# MS20v2.net
KiCad netlist of a schematic drawn in EAGLE
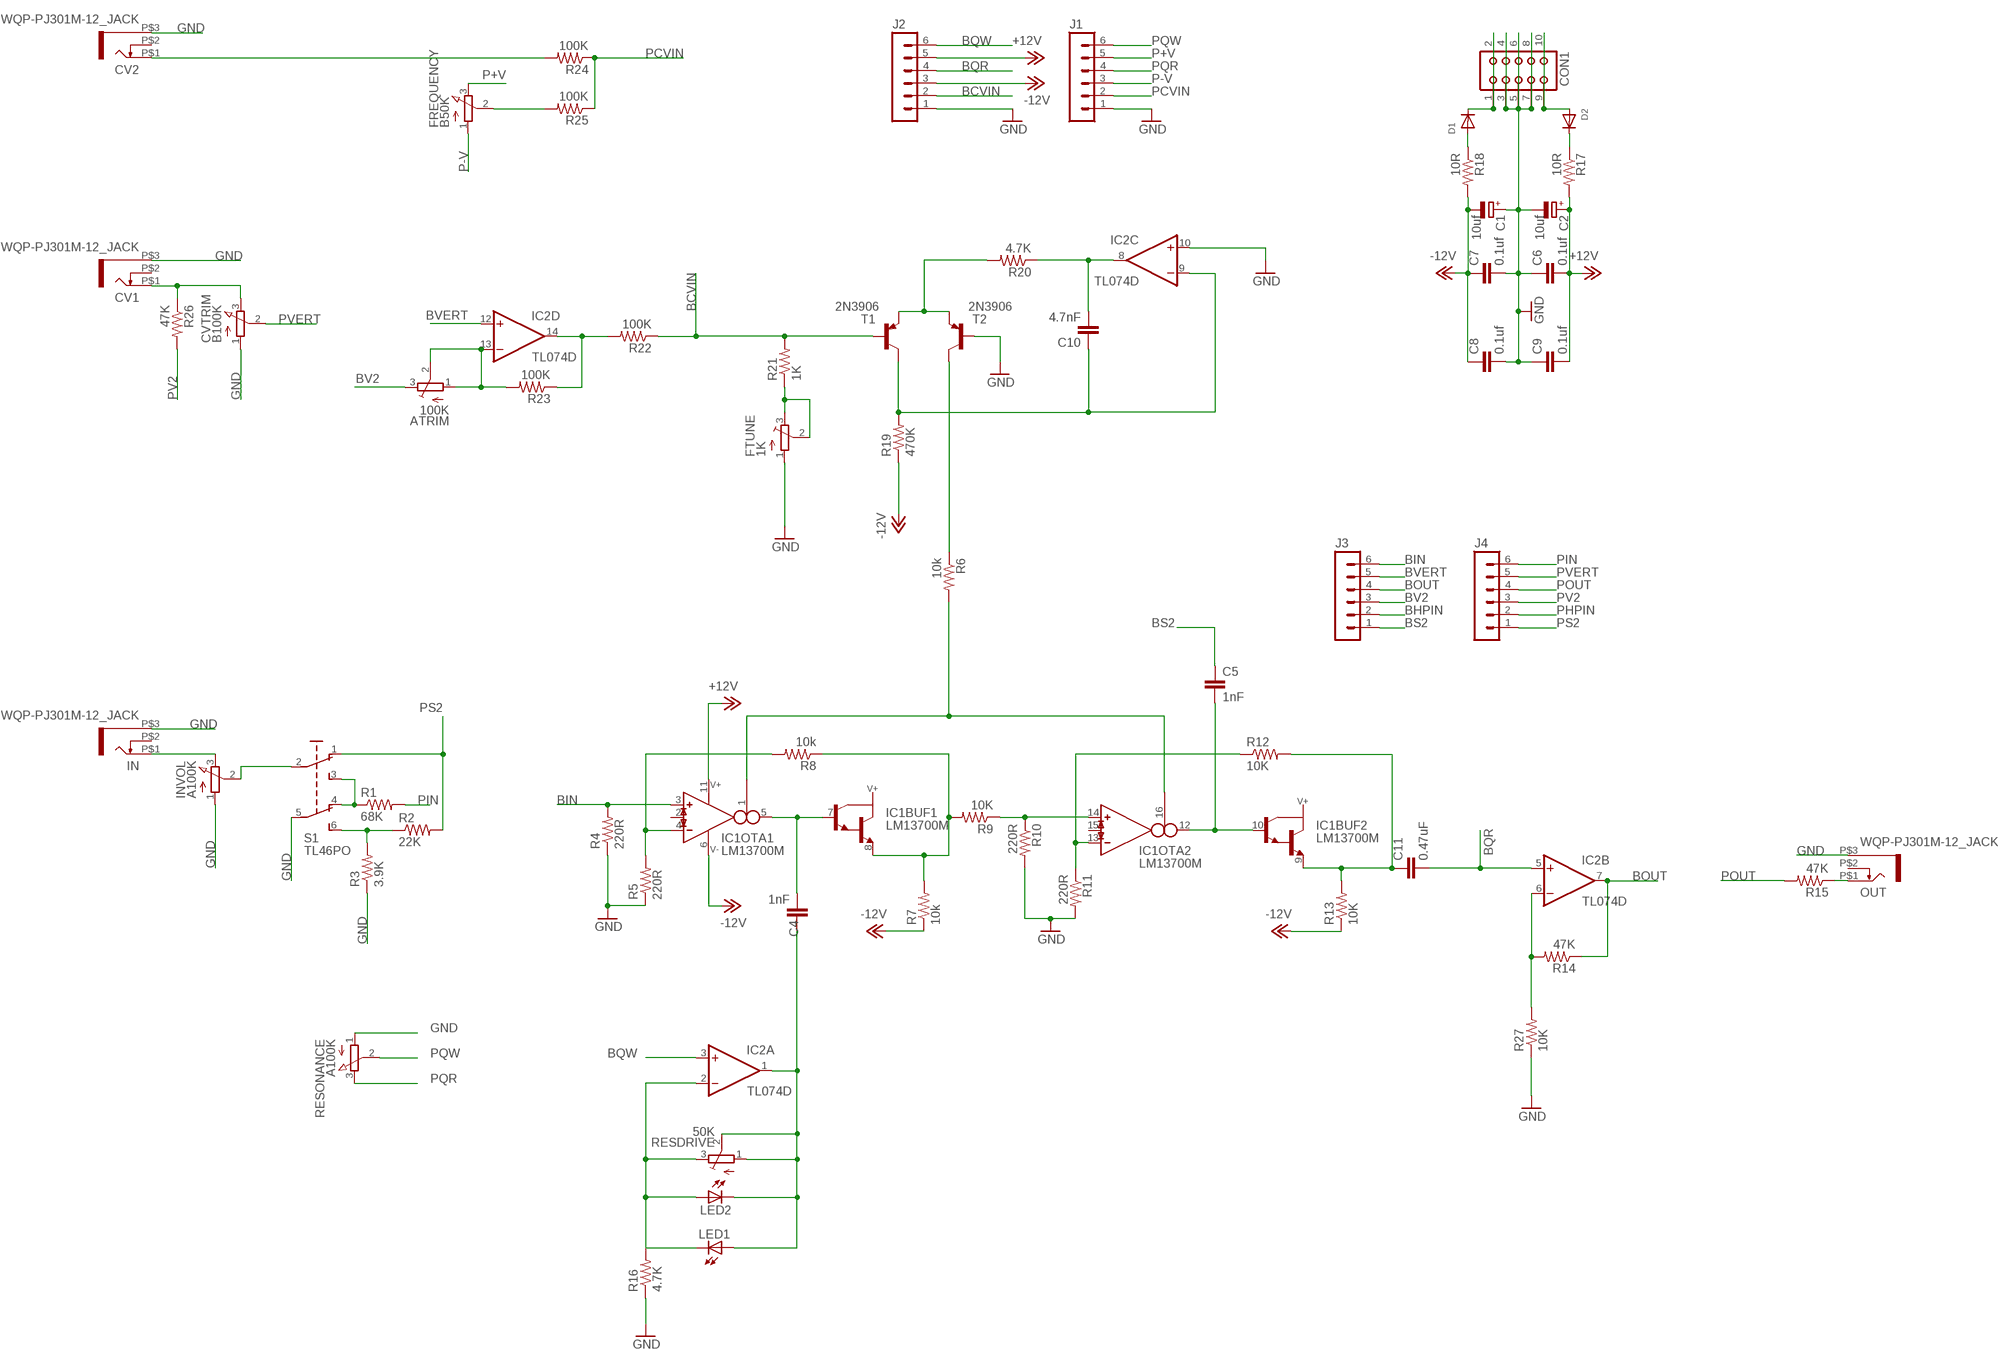
[diagram p0: schematic, sheet 1]

(export (version "E")
  (design (tool "Eeschema 10.0.6"))
  (components
    (comp (ref "ATRIM")
      (value "100K")
      (footprint "eagle-import:TC33X")
      (libsource (lib "eagle-import") (part "TRIMPOTTC33X"))
    )
    (comp (ref "C1")
      (value "10uf")
      (footprint "eagle-import:153CLV-0405")
      (libsource (lib "eagle-import") (part "CPOL-EU153CLV-0405"))
    )
    (comp (ref "C2")
      (value "10uf")
      (footprint "eagle-import:153CLV-0405")
      (libsource (lib "eagle-import") (part "CPOL-EU153CLV-0405"))
    )
    (comp (ref "C4")
      (value "1nF")
      (footprint "eagle-import:C0603")
      (libsource (lib "eagle-import") (part "C-EUC0603"))
    )
    (comp (ref "C5")
      (value "1nF")
      (footprint "eagle-import:C0603")
      (libsource (lib "eagle-import") (part "C-EUC0603"))
    )
    (comp (ref "C6")
      (value "0.1uf")
      (footprint "eagle-import:C0603")
      (libsource (lib "eagle-import") (part "C-EUC0603"))
    )
    (comp (ref "C7")
      (value "0.1uf")
      (footprint "eagle-import:C0603")
      (libsource (lib "eagle-import") (part "C-EUC0603"))
    )
    (comp (ref "C8")
      (value "0.1uf")
      (footprint "eagle-import:C0603")
      (libsource (lib "eagle-import") (part "C-EUC0603"))
    )
    (comp (ref "C9")
      (value "0.1uf")
      (footprint "eagle-import:C0603")
      (libsource (lib "eagle-import") (part "C-EUC0603"))
    )
    (comp (ref "C10")
      (value "4.7nF")
      (footprint "eagle-import:C0603")
      (libsource (lib "eagle-import") (part "C-EUC0603"))
    )
    (comp (ref "C11")
      (value "0.47uF")
      (footprint "eagle-import:C0603")
      (libsource (lib "eagle-import") (part "C-EUC0603"))
    )
    (comp (ref "CON1")
      (value "CON10")
      (footprint "eagle-import:CON10")
      (libsource (lib "eagle-import") (part "CON10"))
    )
    (comp (ref "CV1")
      (value "WQP-PJ301M-12_JACK")
      (footprint "eagle-import:WQP-PJ301M-12_JACK")
      (libsource (lib "eagle-import") (part "WQP-PJ301M-12_JACK"))
    )
    (comp (ref "CV2")
      (value "WQP-PJ301M-12_JACK")
      (footprint "eagle-import:WQP-PJ301M-12_JACK")
      (libsource (lib "eagle-import") (part "WQP-PJ301M-12_JACK"))
    )
    (comp (ref "CVTRIM")
      (value "B100K")
      (footprint "eagle-import:EVUF")
      (libsource (lib "eagle-import") (part "EVUAF2"))
    )
    (comp (ref "D1")
      (value "DIODESOD-123")
      (footprint "eagle-import:SOD-123")
      (libsource (lib "eagle-import") (part "DIODESOD-123"))
    )
    (comp (ref "D2")
      (value "DIODESOD-123")
      (footprint "eagle-import:SOD-123")
      (libsource (lib "eagle-import") (part "DIODESOD-123"))
    )
    (comp (ref "FREQUENCY")
      (value "B50K")
      (footprint "eagle-import:EVUF")
      (libsource (lib "eagle-import") (part "EVUAF2"))
    )
    (comp (ref "FTUNE")
      (value "1K")
      (footprint "eagle-import:TC33X")
      (libsource (lib "eagle-import") (part "TRIMPOTTC33X"))
    )
    (comp (ref "IC1")
      (value "LM13700M")
      (footprint "eagle-import:SO16")
      (libsource (lib "eagle-import") (part "LM13700M"))
    )
    (comp (ref "IC2")
      (value "TL074D")
      (footprint "eagle-import:SO14")
      (libsource (lib "eagle-import") (part "TL074D"))
    )
    (comp (ref "IN")
      (value "WQP-PJ301M-12_JACK")
      (footprint "eagle-import:WQP-PJ301M-12_JACK")
      (libsource (lib "eagle-import") (part "WQP-PJ301M-12_JACK"))
    )
    (comp (ref "INVOL")
      (value "A100K")
      (footprint "eagle-import:EVUF")
      (libsource (lib "eagle-import") (part "EVUAF2"))
    )
    (comp (ref "J1")
      (value "MA06-1")
      (footprint "eagle-import:MA06-1")
      (libsource (lib "eagle-import") (part "MA06-1"))
    )
    (comp (ref "J2")
      (value "MA06-1")
      (footprint "eagle-import:MA06-1")
      (libsource (lib "eagle-import") (part "MA06-1"))
    )
    (comp (ref "J3")
      (value "MA06-1")
      (footprint "eagle-import:MA06-1")
      (libsource (lib "eagle-import") (part "MA06-1"))
    )
    (comp (ref "J4")
      (value "MA06-1")
      (footprint "eagle-import:MA06-1")
      (libsource (lib "eagle-import") (part "MA06-1"))
    )
    (comp (ref "LED1")
      (value "LED3MM")
      (footprint "eagle-import:LED3MM")
      (libsource (lib "eagle-import") (part "LED3MM"))
    )
    (comp (ref "LED2")
      (value "LED3MM")
      (footprint "eagle-import:LED3MM")
      (libsource (lib "eagle-import") (part "LED3MM"))
    )
    (comp (ref "OUT")
      (value "WQP-PJ301M-12_JACK")
      (footprint "eagle-import:WQP-PJ301M-12_JACK")
      (libsource (lib "eagle-import") (part "WQP-PJ301M-12_JACK"))
    )
    (comp (ref "R1")
      (value "68K")
      (footprint "eagle-import:R0603")
      (libsource (lib "eagle-import") (part "R-US_R0603"))
    )
    (comp (ref "R2")
      (value "22K")
      (footprint "eagle-import:R0603")
      (libsource (lib "eagle-import") (part "R-US_R0603"))
    )
    (comp (ref "R3")
      (value "3.9K")
      (footprint "eagle-import:R0603")
      (libsource (lib "eagle-import") (part "R-US_R0603"))
    )
    (comp (ref "R4")
      (value "220R")
      (footprint "eagle-import:R0603")
      (libsource (lib "eagle-import") (part "R-US_R0603"))
    )
    (comp (ref "R5")
      (value "220R")
      (footprint "eagle-import:R0603")
      (libsource (lib "eagle-import") (part "R-US_R0603"))
    )
    (comp (ref "R6")
      (value "10k")
      (footprint "eagle-import:R0603")
      (libsource (lib "eagle-import") (part "R-US_R0603"))
    )
    (comp (ref "R7")
      (value "10k")
      (footprint "eagle-import:R0603")
      (libsource (lib "eagle-import") (part "R-US_R0603"))
    )
    (comp (ref "R8")
      (value "10k")
      (footprint "eagle-import:R0603")
      (libsource (lib "eagle-import") (part "R-US_R0603"))
    )
    (comp (ref "R9")
      (value "10K")
      (footprint "eagle-import:R0603")
      (libsource (lib "eagle-import") (part "R-US_R0603"))
    )
    (comp (ref "R10")
      (value "220R")
      (footprint "eagle-import:R0603")
      (libsource (lib "eagle-import") (part "R-US_R0603"))
    )
    (comp (ref "R11")
      (value "220R")
      (footprint "eagle-import:R0603")
      (libsource (lib "eagle-import") (part "R-US_R0603"))
    )
    (comp (ref "R12")
      (value "10K")
      (footprint "eagle-import:R0603")
      (libsource (lib "eagle-import") (part "R-US_R0603"))
    )
    (comp (ref "R13")
      (value "10K")
      (footprint "eagle-import:R0603")
      (libsource (lib "eagle-import") (part "R-US_R0603"))
    )
    (comp (ref "R14")
      (value "47K")
      (footprint "eagle-import:R0603")
      (libsource (lib "eagle-import") (part "R-US_R0603"))
    )
    (comp (ref "R15")
      (value "47K")
      (footprint "eagle-import:R0603")
      (libsource (lib "eagle-import") (part "R-US_R0603"))
    )
    (comp (ref "R16")
      (value "4.7K")
      (footprint "eagle-import:R0603")
      (libsource (lib "eagle-import") (part "R-US_R0603"))
    )
    (comp (ref "R17")
      (value "10R")
      (footprint "eagle-import:R0603")
      (libsource (lib "eagle-import") (part "R-US_R0603"))
    )
    (comp (ref "R18")
      (value "10R")
      (footprint "eagle-import:R0603")
      (libsource (lib "eagle-import") (part "R-US_R0603"))
    )
    (comp (ref "R19")
      (value "470K")
      (footprint "eagle-import:R0603")
      (libsource (lib "eagle-import") (part "R-US_R0603"))
    )
    (comp (ref "R20")
      (value "4.7K")
      (footprint "eagle-import:R0603")
      (libsource (lib "eagle-import") (part "R-US_R0603"))
    )
    (comp (ref "R21")
      (value "1K")
      (footprint "eagle-import:R0603")
      (libsource (lib "eagle-import") (part "R-US_R0603"))
    )
    (comp (ref "R22")
      (value "100K")
      (footprint "eagle-import:R0603")
      (libsource (lib "eagle-import") (part "R-US_R0603"))
    )
    (comp (ref "R23")
      (value "100K")
      (footprint "eagle-import:R0603")
      (libsource (lib "eagle-import") (part "R-US_R0603"))
    )
    (comp (ref "R24")
      (value "100K")
      (footprint "eagle-import:R0603")
      (libsource (lib "eagle-import") (part "R-US_R0603"))
    )
    (comp (ref "R25")
      (value "100K")
      (footprint "eagle-import:R0603")
      (libsource (lib "eagle-import") (part "R-US_R0603"))
    )
    (comp (ref "R26")
      (value "47K")
      (footprint "eagle-import:R0603")
      (libsource (lib "eagle-import") (part "R-US_R0603"))
    )
    (comp (ref "R27")
      (value "10K")
      (footprint "eagle-import:R0603")
      (libsource (lib "eagle-import") (part "R-US_R0603"))
    )
    (comp (ref "RESDRIVE")
      (value "50K")
      (footprint "eagle-import:TC33X")
      (libsource (lib "eagle-import") (part "TRIMPOTTC33X"))
    )
    (comp (ref "RESONANCE")
      (value "A100K")
      (footprint "eagle-import:EVUF")
      (libsource (lib "eagle-import") (part "EVUAF2"))
    )
    (comp (ref "S1")
      (value "TL46PO")
      (footprint "eagle-import:TL4XPO")
      (libsource (lib "eagle-import") (part "TL46PO"))
    )
    (comp (ref "T1")
      (value "2N3906")
      (footprint "eagle-import:SOT23-BEC")
      (libsource (lib "eagle-import") (part "-PNP-SOT23-BECMMBT3906LT1"))
    )
    (comp (ref "T2")
      (value "2N3906")
      (footprint "eagle-import:SOT23-BEC")
      (libsource (lib "eagle-import") (part "-PNP-SOT23-BECMMBT3906LT1"))
    )
  )
  (nets
    (net (code "1") (name "+12V") (class "Default")
      (node (ref "C2") (pin "+") (pinfunction "+_+") (pintype "passive"))
      (node (ref "C6") (pin "2") (pinfunction "2_2") (pintype "passive"))
      (node (ref "C9") (pin "2") (pinfunction "2_2") (pintype "passive"))
      (node (ref "IC1") (pin "11") (pinfunction "V+_11") (pintype "power_in"))
      (node (ref "J2") (pin "5") (pinfunction "5_5") (pintype "passive"))
      (node (ref "R17") (pin "2") (pinfunction "2_2") (pintype "passive"))
    )
    (net (code "2") (name "-12V") (class "Default")
      (node (ref "C1") (pin "-") (pinfunction "-_-") (pintype "passive"))
      (node (ref "C7") (pin "1") (pinfunction "1_1") (pintype "passive"))
      (node (ref "C8") (pin "1") (pinfunction "1_1") (pintype "passive"))
      (node (ref "IC1") (pin "6") (pinfunction "V-_6") (pintype "power_in"))
      (node (ref "J2") (pin "3") (pinfunction "3_3") (pintype "passive"))
      (node (ref "R13") (pin "1") (pinfunction "1_1") (pintype "passive"))
      (node (ref "R18") (pin "2") (pinfunction "2_2") (pintype "passive"))
      (node (ref "R19") (pin "1") (pinfunction "1_1") (pintype "passive"))
      (node (ref "R7") (pin "1") (pinfunction "1_1") (pintype "passive"))
    )
    (net (code "3") (name "/BCVIN") (class "Default")
      (node (ref "J2") (pin "2") (pinfunction "2_2") (pintype "passive"))
      (node (ref "R21") (pin "2") (pinfunction "2_2") (pintype "passive"))
      (node (ref "R22") (pin "1") (pinfunction "1_1") (pintype "passive"))
      (node (ref "T1") (pin "B") (pinfunction "B_B") (pintype "passive"))
    )
    (net (code "4") (name "/BHPIN") (class "Default")
      (node (ref "J3") (pin "2") (pinfunction "2_2") (pintype "passive"))
    )
    (net (code "5") (name "/BIN") (class "Default")
      (node (ref "IC1") (pin "3") (pinfunction "IN_P_3") (pintype "input"))
      (node (ref "J3") (pin "6") (pinfunction "6_6") (pintype "passive"))
      (node (ref "R4") (pin "2") (pinfunction "2_2") (pintype "passive"))
    )
    (net (code "6") (name "/BOUT") (class "Default")
      (node (ref "IC2") (pin "7") (pinfunction "OUT_7") (pintype "output"))
      (node (ref "J3") (pin "4") (pinfunction "4_4") (pintype "passive"))
      (node (ref "R14") (pin "1") (pinfunction "1_1") (pintype "passive"))
    )
    (net (code "7") (name "/BQR") (class "Default")
      (node (ref "C11") (pin "2") (pinfunction "2_2") (pintype "passive"))
      (node (ref "IC2") (pin "5") (pinfunction "+IN_5") (pintype "input"))
      (node (ref "J2") (pin "4") (pinfunction "4_4") (pintype "passive"))
    )
    (net (code "8") (name "/BQW") (class "Default")
      (node (ref "IC2") (pin "3") (pinfunction "+IN_3") (pintype "input"))
      (node (ref "J2") (pin "6") (pinfunction "6_6") (pintype "passive"))
    )
    (net (code "9") (name "/BS2") (class "Default")
      (node (ref "C5") (pin "1") (pinfunction "1_1") (pintype "passive"))
      (node (ref "J3") (pin "1") (pinfunction "1_1") (pintype "passive"))
    )
    (net (code "10") (name "/BV2") (class "Default")
      (node (ref "ATRIM") (pin "3") (pinfunction "E_3") (pintype "passive"))
      (node (ref "J3") (pin "3") (pinfunction "3_3") (pintype "passive"))
    )
    (net (code "11") (name "/BVERT") (class "Default")
      (node (ref "IC2") (pin "12") (pinfunction "+IN_12") (pintype "input"))
      (node (ref "J3") (pin "5") (pinfunction "5_5") (pintype "passive"))
    )
    (net (code "12") (name "/P+V") (class "Default")
      (node (ref "FREQUENCY") (pin "3") (pinfunction "E_3") (pintype "passive"))
      (node (ref "J1") (pin "5") (pinfunction "5_5") (pintype "passive"))
    )
    (net (code "13") (name "/P-V") (class "Default")
      (node (ref "FREQUENCY") (pin "1") (pinfunction "A_1") (pintype "passive"))
      (node (ref "J1") (pin "3") (pinfunction "3_3") (pintype "passive"))
    )
    (net (code "14") (name "/PCVIN") (class "Default")
      (node (ref "J1") (pin "2") (pinfunction "2_2") (pintype "passive"))
      (node (ref "R24") (pin "1") (pinfunction "1_1") (pintype "passive"))
      (node (ref "R25") (pin "1") (pinfunction "1_1") (pintype "passive"))
    )
    (net (code "15") (name "/PHPIN") (class "Default")
      (node (ref "J4") (pin "2") (pinfunction "2_2") (pintype "passive"))
    )
    (net (code "16") (name "/PIN") (class "Default")
      (node (ref "J4") (pin "6") (pinfunction "6_6") (pintype "passive"))
      (node (ref "R1") (pin "2") (pinfunction "2_2") (pintype "passive"))
    )
    (net (code "17") (name "/POUT") (class "Default")
      (node (ref "J4") (pin "4") (pinfunction "4_4") (pintype "passive"))
      (node (ref "R15") (pin "2") (pinfunction "2_2") (pintype "passive"))
    )
    (net (code "18") (name "/PQR") (class "Default")
      (node (ref "J1") (pin "4") (pinfunction "4_4") (pintype "passive"))
      (node (ref "RESONANCE") (pin "3") (pinfunction "E_3") (pintype "passive"))
    )
    (net (code "19") (name "/PQW") (class "Default")
      (node (ref "J1") (pin "6") (pinfunction "6_6") (pintype "passive"))
      (node (ref "RESONANCE") (pin "2") (pinfunction "S_2") (pintype "passive"))
    )
    (net (code "20") (name "/PS2") (class "Default")
      (node (ref "J4") (pin "1") (pinfunction "1_1") (pintype "passive"))
      (node (ref "R2") (pin "2") (pinfunction "2_2") (pintype "passive"))
      (node (ref "S1") (pin "1") (pinfunction "O_1") (pintype "passive"))
    )
    (net (code "21") (name "/PV2") (class "Default")
      (node (ref "J4") (pin "3") (pinfunction "3_3") (pintype "passive"))
      (node (ref "R26") (pin "2") (pinfunction "2_2") (pintype "passive"))
    )
    (net (code "22") (name "/PVERT") (class "Default")
      (node (ref "CVTRIM") (pin "2") (pinfunction "S_2") (pintype "passive"))
      (node (ref "J4") (pin "5") (pinfunction "5_5") (pintype "passive"))
    )
    (net (code "23") (name "GND") (class "Default")
      (node (ref "C1") (pin "+") (pinfunction "+_+") (pintype "passive"))
      (node (ref "C2") (pin "-") (pinfunction "-_-") (pintype "passive"))
      (node (ref "C6") (pin "1") (pinfunction "1_1") (pintype "passive"))
      (node (ref "C7") (pin "2") (pinfunction "2_2") (pintype "passive"))
      (node (ref "C8") (pin "2") (pinfunction "2_2") (pintype "passive"))
      (node (ref "C9") (pin "1") (pinfunction "1_1") (pintype "passive"))
      (node (ref "CON1") (pin "3") (pinfunction "3_3") (pintype "passive"))
      (node (ref "CON1") (pin "4") (pinfunction "4_4") (pintype "passive"))
      (node (ref "CON1") (pin "5") (pinfunction "5_5") (pintype "passive"))
      (node (ref "CON1") (pin "6") (pinfunction "6_6") (pintype "passive"))
      (node (ref "CON1") (pin "7") (pinfunction "7_7") (pintype "passive"))
      (node (ref "CON1") (pin "8") (pinfunction "8_8") (pintype "passive"))
      (node (ref "CV1") (pin "P$3") (pinfunction "1_P$3") (pintype "passive"))
      (node (ref "CV2") (pin "P$3") (pinfunction "1_P$3") (pintype "passive"))
      (node (ref "CVTRIM") (pin "1") (pinfunction "A_1") (pintype "passive"))
      (node (ref "FTUNE") (pin "1") (pinfunction "A_1") (pintype "passive"))
      (node (ref "IC2") (pin "10") (pinfunction "+IN_10") (pintype "input"))
      (node (ref "IN") (pin "P$3") (pinfunction "1_P$3") (pintype "passive"))
      (node (ref "INVOL") (pin "1") (pinfunction "A_1") (pintype "passive"))
      (node (ref "J1") (pin "1") (pinfunction "1_1") (pintype "passive"))
      (node (ref "J2") (pin "1") (pinfunction "1_1") (pintype "passive"))
      (node (ref "OUT") (pin "P$3") (pinfunction "1_P$3") (pintype "passive"))
      (node (ref "R10") (pin "2") (pinfunction "2_2") (pintype "passive"))
      (node (ref "R11") (pin "2") (pinfunction "2_2") (pintype "passive"))
      (node (ref "R16") (pin "1") (pinfunction "1_1") (pintype "passive"))
      (node (ref "R27") (pin "1") (pinfunction "1_1") (pintype "passive"))
      (node (ref "R3") (pin "1") (pinfunction "1_1") (pintype "passive"))
      (node (ref "R4") (pin "1") (pinfunction "1_1") (pintype "passive"))
      (node (ref "R5") (pin "1") (pinfunction "1_1") (pintype "passive"))
      (node (ref "RESONANCE") (pin "1") (pinfunction "A_1") (pintype "passive"))
      (node (ref "S1") (pin "5") (pinfunction "P1_5") (pintype "passive"))
      (node (ref "T2") (pin "B") (pinfunction "B_B") (pintype "passive"))
    )
    (net (code "24") (name "Net-(ATRIM-A)") (class "Default")
      (node (ref "ATRIM") (pin "1") (pinfunction "A_1") (pintype "passive"))
      (node (ref "ATRIM") (pin "2") (pinfunction "S_2") (pintype "passive"))
      (node (ref "IC2") (pin "13") (pinfunction "-IN_13") (pintype "input"))
      (node (ref "R23") (pin "2") (pinfunction "2_2") (pintype "passive"))
    )
    (net (code "25") (name "Net-(CON1-Pad1)") (class "Default")
      (node (ref "CON1") (pin "1") (pinfunction "1_1") (pintype "passive"))
      (node (ref "CON1") (pin "2") (pinfunction "2_2") (pintype "passive"))
      (node (ref "D1") (pin "C") (pinfunction "C_C") (pintype "passive"))
    )
    (net (code "26") (name "Net-(CON1-Pad10)") (class "Default")
      (node (ref "CON1") (pin "10") (pinfunction "10_10") (pintype "passive"))
      (node (ref "CON1") (pin "9") (pinfunction "9_9") (pintype "passive"))
      (node (ref "D2") (pin "A") (pinfunction "A_A") (pintype "passive"))
    )
    (net (code "27") (name "Net-(CV1-2)") (class "Default")
      (node (ref "CV1") (pin "P$1") (pinfunction "2_P$1") (pintype "passive"))
      (node (ref "CVTRIM") (pin "3") (pinfunction "E_3") (pintype "passive"))
      (node (ref "R26") (pin "1") (pinfunction "1_1") (pintype "passive"))
    )
    (net (code "28") (name "Net-(CV2-2)") (class "Default")
      (node (ref "CV2") (pin "P$1") (pinfunction "2_P$1") (pintype "passive"))
      (node (ref "R24") (pin "2") (pinfunction "2_2") (pintype "passive"))
    )
    (net (code "29") (name "Net-(D1-PadA)") (class "Default")
      (node (ref "D1") (pin "A") (pinfunction "A_A") (pintype "passive"))
      (node (ref "R18") (pin "1") (pinfunction "1_1") (pintype "passive"))
    )
    (net (code "30") (name "Net-(D2-PadC)") (class "Default")
      (node (ref "D2") (pin "C") (pinfunction "C_C") (pintype "passive"))
      (node (ref "R17") (pin "1") (pinfunction "1_1") (pintype "passive"))
    )
    (net (code "31") (name "Net-(FREQUENCY-S)") (class "Default")
      (node (ref "FREQUENCY") (pin "2") (pinfunction "S_2") (pintype "passive"))
      (node (ref "R25") (pin "2") (pinfunction "2_2") (pintype "passive"))
    )
    (net (code "32") (name "Net-(FTUNE-E)") (class "Default")
      (node (ref "FTUNE") (pin "2") (pinfunction "S_2") (pintype "passive"))
      (node (ref "FTUNE") (pin "3") (pinfunction "E_3") (pintype "passive"))
      (node (ref "R21") (pin "1") (pinfunction "1_1") (pintype "passive"))
    )
    (net (code "33") (name "Net-(IC1A-B)") (class "Default")
      (node (ref "C4") (pin "2") (pinfunction "2_2") (pintype "passive"))
      (node (ref "IC1") (pin "5") (pinfunction "OUT_5") (pintype "output"))
      (node (ref "IC1") (pin "7") (pinfunction "B_7") (pintype "passive"))
    )
    (net (code "34") (name "Net-(IC1A-E)") (class "Default")
      (node (ref "IC1") (pin "8") (pinfunction "E_8") (pintype "passive"))
      (node (ref "R7") (pin "2") (pinfunction "2_2") (pintype "passive"))
      (node (ref "R8") (pin "1") (pinfunction "1_1") (pintype "passive"))
      (node (ref "R9") (pin "2") (pinfunction "2_2") (pintype "passive"))
    )
    (net (code "35") (name "Net-(IC1B-B)") (class "Default")
      (node (ref "C5") (pin "2") (pinfunction "2_2") (pintype "passive"))
      (node (ref "IC1") (pin "10") (pinfunction "B_10") (pintype "passive"))
      (node (ref "IC1") (pin "12") (pinfunction "OUT_12") (pintype "output"))
    )
    (net (code "36") (name "Net-(IC1B-E)") (class "Default")
      (node (ref "C11") (pin "1") (pinfunction "1_1") (pintype "passive"))
      (node (ref "IC1") (pin "9") (pinfunction "E_9") (pintype "passive"))
      (node (ref "R12") (pin "2") (pinfunction "2_2") (pintype "passive"))
      (node (ref "R13") (pin "2") (pinfunction "2_2") (pintype "passive"))
    )
    (net (code "37") (name "Net-(IC1C-IN_N)") (class "Default")
      (node (ref "IC1") (pin "4") (pinfunction "IN_N_4") (pintype "input"))
      (node (ref "R5") (pin "2") (pinfunction "2_2") (pintype "passive"))
      (node (ref "R8") (pin "2") (pinfunction "2_2") (pintype "passive"))
    )
    (net (code "38") (name "Net-(IC1C-I_BIAS)") (class "Default")
      (node (ref "IC1") (pin "1") (pinfunction "I_BIAS_1") (pintype "input"))
      (node (ref "IC1") (pin "16") (pinfunction "I_BIAS_16") (pintype "input"))
      (node (ref "R6") (pin "2") (pinfunction "2_2") (pintype "passive"))
    )
    (net (code "39") (name "Net-(IC1D-IN_N)") (class "Default")
      (node (ref "IC1") (pin "13") (pinfunction "IN_N_13") (pintype "input"))
      (node (ref "R11") (pin "1") (pinfunction "1_1") (pintype "passive"))
      (node (ref "R12") (pin "1") (pinfunction "1_1") (pintype "passive"))
    )
    (net (code "40") (name "Net-(IC1D-IN_P)") (class "Default")
      (node (ref "IC1") (pin "14") (pinfunction "IN_P_14") (pintype "input"))
      (node (ref "R10") (pin "1") (pinfunction "1_1") (pintype "passive"))
      (node (ref "R9") (pin "1") (pinfunction "1_1") (pintype "passive"))
    )
    (net (code "41") (name "Net-(IC2A--IN)") (class "Default")
      (node (ref "IC2") (pin "2") (pinfunction "-IN_2") (pintype "input"))
      (node (ref "LED1") (pin "K") (pinfunction "C_K") (pintype "passive"))
      (node (ref "LED2") (pin "A") (pinfunction "A_A") (pintype "passive"))
      (node (ref "R16") (pin "2") (pinfunction "2_2") (pintype "passive"))
      (node (ref "RESDRIVE") (pin "3") (pinfunction "E_3") (pintype "passive"))
    )
    (net (code "42") (name "Net-(IC2A-OUT)") (class "Default")
      (node (ref "C4") (pin "1") (pinfunction "1_1") (pintype "passive"))
      (node (ref "IC2") (pin "1") (pinfunction "OUT_1") (pintype "output"))
      (node (ref "LED1") (pin "A") (pinfunction "A_A") (pintype "passive"))
      (node (ref "LED2") (pin "K") (pinfunction "C_K") (pintype "passive"))
      (node (ref "RESDRIVE") (pin "1") (pinfunction "A_1") (pintype "passive"))
      (node (ref "RESDRIVE") (pin "2") (pinfunction "S_2") (pintype "passive"))
    )
    (net (code "43") (name "Net-(IC2B--IN)") (class "Default")
      (node (ref "IC2") (pin "6") (pinfunction "-IN_6") (pintype "input"))
      (node (ref "R14") (pin "2") (pinfunction "2_2") (pintype "passive"))
      (node (ref "R27") (pin "2") (pinfunction "2_2") (pintype "passive"))
    )
    (net (code "44") (name "Net-(IC2C--IN)") (class "Default")
      (node (ref "C10") (pin "1") (pinfunction "1_1") (pintype "passive"))
      (node (ref "IC2") (pin "9") (pinfunction "-IN_9") (pintype "input"))
      (node (ref "R19") (pin "2") (pinfunction "2_2") (pintype "passive"))
      (node (ref "T1") (pin "C") (pinfunction "C_C") (pintype "passive"))
    )
    (net (code "45") (name "Net-(IC2C-OUT)") (class "Default")
      (node (ref "C10") (pin "2") (pinfunction "2_2") (pintype "passive"))
      (node (ref "IC2") (pin "8") (pinfunction "OUT_8") (pintype "output"))
      (node (ref "R20") (pin "1") (pinfunction "1_1") (pintype "passive"))
    )
    (net (code "46") (name "Net-(IC2D-OUT)") (class "Default")
      (node (ref "IC2") (pin "14") (pinfunction "OUT_14") (pintype "output"))
      (node (ref "R22") (pin "2") (pinfunction "2_2") (pintype "passive"))
      (node (ref "R23") (pin "1") (pinfunction "1_1") (pintype "passive"))
    )
    (net (code "47") (name "Net-(IN-2)") (class "Default")
      (node (ref "IN") (pin "P$1") (pinfunction "2_P$1") (pintype "passive"))
      (node (ref "INVOL") (pin "3") (pinfunction "E_3") (pintype "passive"))
    )
    (net (code "48") (name "Net-(INVOL-S)") (class "Default")
      (node (ref "INVOL") (pin "2") (pinfunction "S_2") (pintype "passive"))
      (node (ref "S1") (pin "2") (pinfunction "P_2") (pintype "passive"))
    )
    (net (code "49") (name "Net-(OUT-2)") (class "Default")
      (node (ref "OUT") (pin "P$1") (pinfunction "2_P$1") (pintype "passive"))
      (node (ref "R15") (pin "1") (pinfunction "1_1") (pintype "passive"))
    )
    (net (code "50") (name "Net-(R6-Pad1)") (class "Default")
      (node (ref "R6") (pin "1") (pinfunction "1_1") (pintype "passive"))
      (node (ref "T2") (pin "C") (pinfunction "C_C") (pintype "passive"))
    )
    (net (code "51") (name "Net-(R20-Pad2)") (class "Default")
      (node (ref "R20") (pin "2") (pinfunction "2_2") (pintype "passive"))
      (node (ref "T1") (pin "E") (pinfunction "E_E") (pintype "passive"))
      (node (ref "T2") (pin "E") (pinfunction "E_E") (pintype "passive"))
    )
    (net (code "52") (name "Net-(S1-O1)") (class "Default")
      (node (ref "R1") (pin "1") (pinfunction "1_1") (pintype "passive"))
      (node (ref "S1") (pin "3") (pinfunction "S_3") (pintype "passive"))
      (node (ref "S1") (pin "4") (pinfunction "O1_4") (pintype "passive"))
    )
    (net (code "53") (name "Net-(S1-S1)") (class "Default")
      (node (ref "R2") (pin "1") (pinfunction "1_1") (pintype "passive"))
      (node (ref "R3") (pin "2") (pinfunction "2_2") (pintype "passive"))
      (node (ref "S1") (pin "6") (pinfunction "S1_6") (pintype "passive"))
    )
    (net (code "54") (name "unconnected-(CV1-3-PadP$2)") (class "Default")
      (node (ref "CV1") (pin "P$2") (pinfunction "3_P$2") (pintype "passive"))
    )
    (net (code "55") (name "unconnected-(CV2-3-PadP$2)") (class "Default")
      (node (ref "CV2") (pin "P$2") (pinfunction "3_P$2") (pintype "passive"))
    )
    (net (code "56") (name "unconnected-(IC1C-I_DIODE-Pad2)") (class "Default")
      (node (ref "IC1") (pin "2") (pinfunction "I_DIODE_2") (pintype "input"))
    )
    (net (code "57") (name "unconnected-(IC1D-I_DIODE-Pad15)") (class "Default")
      (node (ref "IC1") (pin "15") (pinfunction "I_DIODE_15") (pintype "input"))
    )
    (net (code "58") (name "unconnected-(IN-3-PadP$2)") (class "Default")
      (node (ref "IN") (pin "P$2") (pinfunction "3_P$2") (pintype "passive"))
    )
    (net (code "59") (name "unconnected-(OUT-3-PadP$2)") (class "Default")
      (node (ref "OUT") (pin "P$2") (pinfunction "3_P$2") (pintype "passive"))
    )
  )
)
